# v1.net
KiCad netlist of a schematic drawn in EAGLE
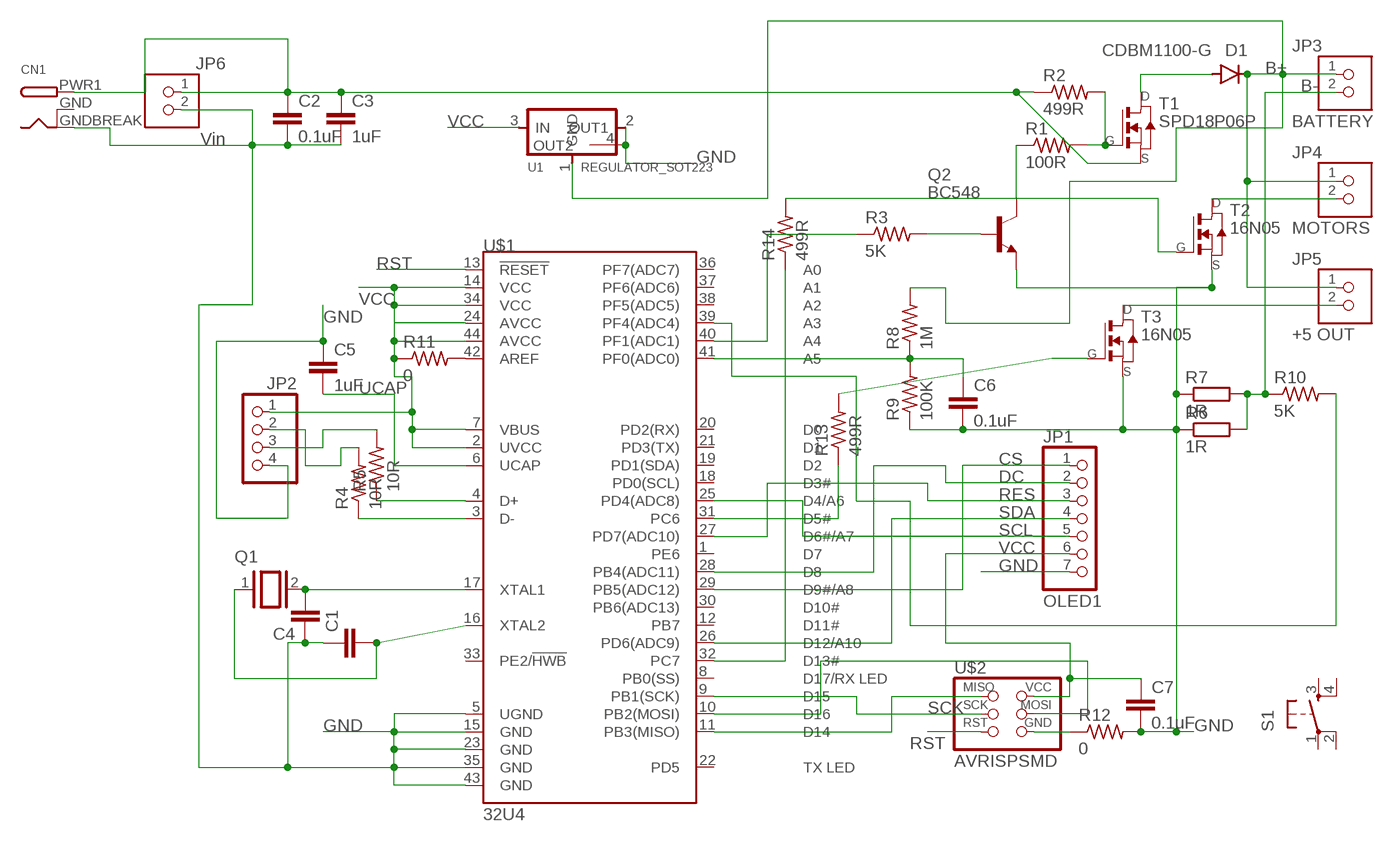
[diagram p0: schematic, sheet 1]

(export (version "E")
  (design (tool "Eeschema 10.0.6"))
  (components
    (comp (ref "C1")
      (value "C-EUC1206")
      (footprint "eagle-import:C1206")
      (libsource (lib "eagle-import") (part "C-EUC1206"))
    )
    (comp (ref "C2")
      (value "0.1uF")
      (footprint "eagle-import:C1206")
      (libsource (lib "eagle-import") (part "C-EUC1206"))
    )
    (comp (ref "C3")
      (value "1uF")
      (footprint "eagle-import:C1206")
      (libsource (lib "eagle-import") (part "C-EUC1206"))
    )
    (comp (ref "C4")
      (value "C-EUC1206")
      (footprint "eagle-import:C1206")
      (libsource (lib "eagle-import") (part "C-EUC1206"))
    )
    (comp (ref "C5")
      (value "1uF")
      (footprint "eagle-import:C1206")
      (libsource (lib "eagle-import") (part "C-EUC1206"))
    )
    (comp (ref "C6")
      (value "0.1uF")
      (footprint "eagle-import:C1206")
      (libsource (lib "eagle-import") (part "C-EUC1206"))
    )
    (comp (ref "C7")
      (value "0.1uF")
      (footprint "eagle-import:C1206")
      (libsource (lib "eagle-import") (part "C-EUC1206"))
    )
    (comp (ref "CN1")
      (value "DCBARRELSMT")
      (footprint "eagle-import:DCJACK_2MM_SMT")
      (libsource (lib "eagle-import") (part "DCBARRELSMT"))
    )
    (comp (ref "D1")
      (value "CDBM1100-G")
      (footprint "eagle-import:MINI-SMA")
      (libsource (lib "eagle-import") (part "CDBM1100-G"))
    )
    (comp (ref "JP1")
      (value "OLED1")
      (footprint "eagle-import:1X07")
      (libsource (lib "eagle-import") (part "PINHD-1X7"))
    )
    (comp (ref "JP2")
      (value "PINHD-1X4")
      (footprint "eagle-import:1X04")
      (libsource (lib "eagle-import") (part "PINHD-1X4"))
    )
    (comp (ref "JP3")
      (value "BATTERY")
      (footprint "eagle-import:ED555DS-2DS")
      (libsource (lib "eagle-import") (part "TERM-1X02-FABLAB"))
    )
    (comp (ref "JP4")
      (value "MOTORS")
      (footprint "eagle-import:ED555DS-2DS")
      (libsource (lib "eagle-import") (part "TERM-1X02-FABLAB"))
    )
    (comp (ref "JP5")
      (value "+5 OUT")
      (footprint "eagle-import:ED555DS-2DS")
      (libsource (lib "eagle-import") (part "TERM-1X02-FABLAB"))
    )
    (comp (ref "JP6")
      (value "Vin")
      (footprint "eagle-import:ED555DS-2DS")
      (libsource (lib "eagle-import") (part "TERM-1X02-FABLAB"))
    )
    (comp (ref "Q1")
      (value "XTAL/S")
      (footprint "eagle-import:QS")
      (libsource (lib "eagle-import") (part "XTAL/S"))
    )
    (comp (ref "Q2")
      (value "BC548")
      (footprint "eagle-import:TO92-EBC")
      (libsource (lib "eagle-import") (part "BC548"))
    )
    (comp (ref "R1")
      (value "100R")
      (footprint "eagle-import:M1206")
      (libsource (lib "eagle-import") (part "R-US_M1206"))
    )
    (comp (ref "R2")
      (value "499R")
      (footprint "eagle-import:M1206")
      (libsource (lib "eagle-import") (part "R-US_M1206"))
    )
    (comp (ref "R3")
      (value "5K")
      (footprint "eagle-import:M1206")
      (libsource (lib "eagle-import") (part "R-US_M1206"))
    )
    (comp (ref "R4")
      (value "10R")
      (footprint "eagle-import:M1206")
      (libsource (lib "eagle-import") (part "R-US_M1206"))
    )
    (comp (ref "R5")
      (value "10R")
      (footprint "eagle-import:M1206")
      (libsource (lib "eagle-import") (part "R-US_M1206"))
    )
    (comp (ref "R6")
      (value "1R")
      (footprint "eagle-import:R6332W")
      (libsource (lib "eagle-import") (part "R-EU_R6332W"))
    )
    (comp (ref "R7")
      (value "1R")
      (footprint "eagle-import:R6332W")
      (libsource (lib "eagle-import") (part "R-EU_R6332W"))
    )
    (comp (ref "R8")
      (value "1M")
      (footprint "eagle-import:M1206")
      (libsource (lib "eagle-import") (part "R-US_M1206"))
    )
    (comp (ref "R9")
      (value "100K")
      (footprint "eagle-import:M1206")
      (libsource (lib "eagle-import") (part "R-US_M1206"))
    )
    (comp (ref "R10")
      (value "5K")
      (footprint "eagle-import:M1206")
      (libsource (lib "eagle-import") (part "R-US_M1206"))
    )
    (comp (ref "R11")
      (value "0")
      (footprint "eagle-import:M1206")
      (libsource (lib "eagle-import") (part "R-US_M1206"))
    )
    (comp (ref "R12")
      (value "0")
      (footprint "eagle-import:M1206")
      (libsource (lib "eagle-import") (part "R-US_M1206"))
    )
    (comp (ref "R13")
      (value "499R")
      (footprint "eagle-import:M1206")
      (libsource (lib "eagle-import") (part "R-US_M1206"))
    )
    (comp (ref "R14")
      (value "499R")
      (footprint "eagle-import:M1206")
      (libsource (lib "eagle-import") (part "R-US_M1206"))
    )
    (comp (ref "S1")
      (value "6MM_SWITCH6MM_SWITCH")
      (footprint "eagle-import:6MM_SWITCH")
      (libsource (lib "eagle-import") (part "6MM_SWITCH6MM_SWITCH"))
    )
    (comp (ref "T1")
      (value "SPD18P06P")
      (footprint "eagle-import:TO252")
      (libsource (lib "eagle-import") (part "NMOSFETTO252"))
    )
    (comp (ref "T2")
      (value "16N05")
      (footprint "eagle-import:TO252")
      (libsource (lib "eagle-import") (part "NMOSFETTO252"))
    )
    (comp (ref "T3")
      (value "16N05")
      (footprint "eagle-import:TO252")
      (libsource (lib "eagle-import") (part "NMOSFETTO252"))
    )
    (comp (ref "U$1")
      (value "32U4")
      (footprint "eagle-import:TQFP44")
      (libsource (lib "eagle-import") (part "ATMEGA32U4TQFP-44"))
    )
    (comp (ref "U$2")
      (value "AVRISPSMD")
      (footprint "eagle-import:2X03SMD")
      (libsource (lib "eagle-import") (part "AVRISPSMD"))
    )
    (comp (ref "U1")
      (value "REGULATOR_SOT223")
      (footprint "eagle-import:SOT223")
      (libsource (lib "eagle-import") (part "REGULATOR_SOT223"))
    )
  )
  (nets
    (net (code "1") (name "/B+") (class "Default")
      (node (ref "D1") (pin "KATHODE") (pinfunction "KATHODE_KATHODE") (pintype "bidirectional"))
      (node (ref "JP3") (pin "1") (pinfunction "1_1") (pintype "passive"))
      (node (ref "JP4") (pin "1") (pinfunction "1_1") (pintype "passive"))
      (node (ref "JP5") (pin "1") (pinfunction "1_1") (pintype "passive"))
      (node (ref "R8") (pin "2") (pinfunction "2_2") (pintype "passive"))
      (node (ref "U1") (pin "1") (pinfunction "GND_1") (pintype "bidirectional"))
    )
    (net (code "2") (name "/B-") (class "Default")
      (node (ref "JP3") (pin "2") (pinfunction "2_2") (pintype "passive"))
      (node (ref "R10") (pin "1") (pinfunction "1_1") (pintype "passive"))
      (node (ref "R6") (pin "2") (pinfunction "2_2") (pintype "passive"))
      (node (ref "R7") (pin "2") (pinfunction "2_2") (pintype "passive"))
    )
    (net (code "3") (name "/CS") (class "Default")
      (node (ref "JP1") (pin "1") (pinfunction "1_1") (pintype "passive"))
      (node (ref "U$1") (pin "29") (pinfunction "PB5(ADC12)_29") (pintype "bidirectional"))
    )
    (net (code "4") (name "/DC") (class "Default")
      (node (ref "JP1") (pin "2") (pinfunction "2_2") (pintype "passive"))
      (node (ref "U$1") (pin "28") (pinfunction "PB4(ADC11)_28") (pintype "bidirectional"))
    )
    (net (code "5") (name "/GND") (class "Default")
      (node (ref "C1") (pin "1") (pinfunction "1_1") (pintype "passive"))
      (node (ref "C2") (pin "2") (pinfunction "2_2") (pintype "passive"))
      (node (ref "C3") (pin "2") (pinfunction "2_2") (pintype "passive"))
      (node (ref "C4") (pin "1") (pinfunction "1_1") (pintype "passive"))
      (node (ref "C5") (pin "1") (pinfunction "1_1") (pintype "passive"))
      (node (ref "C6") (pin "2") (pinfunction "2_2") (pintype "passive"))
      (node (ref "C7") (pin "2") (pinfunction "2_2") (pintype "passive"))
      (node (ref "CN1") (pin "GNDBREAK") (pinfunction "GND_GNDBREAK") (pintype "power_in"))
      (node (ref "JP1") (pin "7") (pinfunction "7_7") (pintype "passive"))
      (node (ref "JP2") (pin "4") (pinfunction "4_4") (pintype "passive"))
      (node (ref "JP6") (pin "2") (pinfunction "2_2") (pintype "passive"))
      (node (ref "Q2") (pin "E") (pinfunction "E_E") (pintype "passive"))
      (node (ref "R12") (pin "2") (pinfunction "2_2") (pintype "passive"))
      (node (ref "R6") (pin "1") (pinfunction "1_1") (pintype "passive"))
      (node (ref "R7") (pin "1") (pinfunction "1_1") (pintype "passive"))
      (node (ref "R9") (pin "1") (pinfunction "1_1") (pintype "passive"))
      (node (ref "T2") (pin "2") (pinfunction "S_2") (pintype "passive"))
      (node (ref "T3") (pin "2") (pinfunction "S_2") (pintype "passive"))
      (node (ref "U$1") (pin "15") (pinfunction "GND_15") (pintype "bidirectional"))
      (node (ref "U$1") (pin "23") (pinfunction "GND_23") (pintype "bidirectional"))
      (node (ref "U$1") (pin "35") (pinfunction "GND_35") (pintype "bidirectional"))
      (node (ref "U$1") (pin "43") (pinfunction "GND_43") (pintype "bidirectional"))
      (node (ref "U$1") (pin "5") (pinfunction "UGND_5") (pintype "bidirectional"))
      (node (ref "U1") (pin "2") (pinfunction "OUT1_2") (pintype "bidirectional"))
      (node (ref "U1") (pin "4") (pinfunction "OUT2_4") (pintype "bidirectional"))
    )
    (net (code "6") (name "/GNDBREAK") (class "Default")
      (node (ref "CN1") (pin "GND") (pinfunction "GNDBREAK_GND") (pintype "power_in"))
    )
    (net (code "7") (name "/RES") (class "Default")
      (node (ref "JP1") (pin "3") (pinfunction "3_3") (pintype "passive"))
      (node (ref "U$1") (pin "27") (pinfunction "PD7(ADC10)_27") (pintype "bidirectional"))
    )
    (net (code "8") (name "/RST") (class "Default")
      (node (ref "U$1") (pin "13") (pinfunction "~{RESET}_13") (pintype "bidirectional"))
      (node (ref "U$2") (pin "5") (pinfunction "RST_5") (pintype "passive"))
    )
    (net (code "9") (name "/SCK") (class "Default")
      (node (ref "U$1") (pin "9") (pinfunction "PB1(SCK)_9") (pintype "bidirectional"))
      (node (ref "U$2") (pin "3") (pinfunction "SCK_3") (pintype "passive"))
    )
    (net (code "10") (name "/SCL") (class "Default")
      (node (ref "JP1") (pin "5") (pinfunction "5_5") (pintype "passive"))
      (node (ref "U$1") (pin "25") (pinfunction "PD4(ADC8)_25") (pintype "bidirectional"))
    )
    (net (code "11") (name "/SDA") (class "Default")
      (node (ref "JP1") (pin "4") (pinfunction "4_4") (pintype "passive"))
      (node (ref "U$1") (pin "26") (pinfunction "PD6(ADC9)_26") (pintype "bidirectional"))
    )
    (net (code "12") (name "/UCAP") (class "Default")
      (node (ref "C5") (pin "2") (pinfunction "2_2") (pintype "passive"))
      (node (ref "U$1") (pin "6") (pinfunction "UCAP_6") (pintype "bidirectional"))
    )
    (net (code "13") (name "/VCC") (class "Default")
      (node (ref "C7") (pin "1") (pinfunction "1_1") (pintype "passive"))
      (node (ref "JP1") (pin "6") (pinfunction "6_6") (pintype "passive"))
      (node (ref "JP2") (pin "1") (pinfunction "1_1") (pintype "passive"))
      (node (ref "R11") (pin "1") (pinfunction "1_1") (pintype "passive"))
      (node (ref "U$1") (pin "14") (pinfunction "VCC_14") (pintype "bidirectional"))
      (node (ref "U$1") (pin "2") (pinfunction "UVCC_2") (pintype "bidirectional"))
      (node (ref "U$1") (pin "24") (pinfunction "AVCC_24") (pintype "bidirectional"))
      (node (ref "U$1") (pin "34") (pinfunction "VCC_34") (pintype "bidirectional"))
      (node (ref "U$1") (pin "44") (pinfunction "AVCC_44") (pintype "bidirectional"))
      (node (ref "U$1") (pin "7") (pinfunction "VBUS_7") (pintype "bidirectional"))
      (node (ref "U$2") (pin "2") (pinfunction "VCC_2") (pintype "passive"))
      (node (ref "U1") (pin "3") (pinfunction "IN_3") (pintype "bidirectional"))
    )
    (net (code "14") (name "Net-(CN1-PWR)") (class "Default")
      (node (ref "C2") (pin "1") (pinfunction "1_1") (pintype "passive"))
      (node (ref "C3") (pin "1") (pinfunction "1_1") (pintype "passive"))
      (node (ref "CN1") (pin "PWR1") (pinfunction "PWR_PWR1") (pintype "power_in"))
      (node (ref "JP6") (pin "1") (pinfunction "1_1") (pintype "passive"))
      (node (ref "R2") (pin "1") (pinfunction "1_1") (pintype "passive"))
      (node (ref "T1") (pin "2") (pinfunction "S_2") (pintype "passive"))
    )
    (net (code "15") (name "Net-(JP2-Pad2)") (class "Default")
      (node (ref "JP2") (pin "2") (pinfunction "2_2") (pintype "passive"))
      (node (ref "R4") (pin "2") (pinfunction "2_2") (pintype "passive"))
    )
    (net (code "16") (name "Net-(JP2-Pad3)") (class "Default")
      (node (ref "JP2") (pin "3") (pinfunction "3_3") (pintype "passive"))
      (node (ref "R5") (pin "2") (pinfunction "2_2") (pintype "passive"))
    )
    (net (code "17") (name "Net-(Q2-PadB)") (class "Default")
      (node (ref "Q2") (pin "B") (pinfunction "B_B") (pintype "passive"))
      (node (ref "R3") (pin "2") (pinfunction "2_2") (pintype "passive"))
    )
    (net (code "18") (name "Net-(Q2-PadC)") (class "Default")
      (node (ref "Q2") (pin "C") (pinfunction "C_C") (pintype "passive"))
      (node (ref "R1") (pin "1") (pinfunction "1_1") (pintype "passive"))
    )
    (net (code "19") (name "Net-(T1-D)") (class "Default")
      (node (ref "D1") (pin "ANODE") (pinfunction "ANODE_ANODE") (pintype "bidirectional"))
      (node (ref "T1") (pin "3") (pinfunction "D_3") (pintype "passive"))
    )
    (net (code "20") (name "Net-(T1-G)") (class "Default")
      (node (ref "R1") (pin "2") (pinfunction "2_2") (pintype "passive"))
      (node (ref "R2") (pin "2") (pinfunction "2_2") (pintype "passive"))
      (node (ref "T1") (pin "1") (pinfunction "G_1") (pintype "passive"))
    )
    (net (code "21") (name "Net-(T2-D)") (class "Default")
      (node (ref "JP4") (pin "2") (pinfunction "2_2") (pintype "passive"))
      (node (ref "T2") (pin "3") (pinfunction "D_3") (pintype "passive"))
    )
    (net (code "22") (name "Net-(T2-G)") (class "Default")
      (node (ref "R14") (pin "2") (pinfunction "2_2") (pintype "passive"))
      (node (ref "T2") (pin "1") (pinfunction "G_1") (pintype "passive"))
    )
    (net (code "23") (name "Net-(T3-D)") (class "Default")
      (node (ref "JP5") (pin "2") (pinfunction "2_2") (pintype "passive"))
      (node (ref "T3") (pin "3") (pinfunction "D_3") (pintype "passive"))
    )
    (net (code "24") (name "Net-(T3-G)") (class "Default")
      (node (ref "R13") (pin "2") (pinfunction "2_2") (pintype "passive"))
      (node (ref "T3") (pin "1") (pinfunction "G_1") (pintype "passive"))
    )
    (net (code "25") (name "Net-(U$1-AREF)") (class "Default")
      (node (ref "R11") (pin "2") (pinfunction "2_2") (pintype "passive"))
      (node (ref "U$1") (pin "42") (pinfunction "AREF_42") (pintype "bidirectional"))
    )
    (net (code "26") (name "Net-(U$1-D+)") (class "Default")
      (node (ref "R5") (pin "1") (pinfunction "1_1") (pintype "passive"))
      (node (ref "U$1") (pin "4") (pinfunction "D+_4") (pintype "bidirectional"))
    )
    (net (code "27") (name "Net-(U$1-D-)") (class "Default")
      (node (ref "R4") (pin "1") (pinfunction "1_1") (pintype "passive"))
      (node (ref "U$1") (pin "3") (pinfunction "D-_3") (pintype "bidirectional"))
    )
    (net (code "28") (name "Net-(U$1-PB2(MOSI))") (class "Default")
      (node (ref "U$1") (pin "10") (pinfunction "PB2(MOSI)_10") (pintype "bidirectional"))
      (node (ref "U$2") (pin "4") (pinfunction "MOSI_4") (pintype "passive"))
    )
    (net (code "29") (name "Net-(U$1-PB3(MISO))") (class "Default")
      (node (ref "U$1") (pin "11") (pinfunction "PB3(MISO)_11") (pintype "bidirectional"))
      (node (ref "U$2") (pin "1") (pinfunction "MISO_1") (pintype "passive"))
    )
    (net (code "30") (name "Net-(U$1-PC6)") (class "Default")
      (node (ref "R13") (pin "1") (pinfunction "1_1") (pintype "passive"))
      (node (ref "U$1") (pin "31") (pinfunction "PC6_31") (pintype "bidirectional"))
    )
    (net (code "31") (name "Net-(U$1-PC7)") (class "Default")
      (node (ref "R14") (pin "1") (pinfunction "1_1") (pintype "passive"))
      (node (ref "U$1") (pin "32") (pinfunction "PC7_32") (pintype "bidirectional"))
    )
    (net (code "32") (name "Net-(U$1-PF0(ADC0))") (class "Default")
      (node (ref "C6") (pin "1") (pinfunction "1_1") (pintype "passive"))
      (node (ref "R8") (pin "1") (pinfunction "1_1") (pintype "passive"))
      (node (ref "R9") (pin "2") (pinfunction "2_2") (pintype "passive"))
      (node (ref "U$1") (pin "41") (pinfunction "PF0(ADC0)_41") (pintype "bidirectional"))
    )
    (net (code "33") (name "Net-(U$1-PF1(ADC1))") (class "Default")
      (node (ref "R3") (pin "1") (pinfunction "1_1") (pintype "passive"))
      (node (ref "U$1") (pin "40") (pinfunction "PF1(ADC1)_40") (pintype "bidirectional"))
    )
    (net (code "34") (name "Net-(U$1-PF4(ADC4))") (class "Default")
      (node (ref "R10") (pin "2") (pinfunction "2_2") (pintype "passive"))
      (node (ref "U$1") (pin "39") (pinfunction "PF4(ADC4)_39") (pintype "bidirectional"))
    )
    (net (code "35") (name "Net-(U$1-XTAL1)") (class "Default")
      (node (ref "C4") (pin "2") (pinfunction "2_2") (pintype "passive"))
      (node (ref "Q1") (pin "2") (pinfunction "2_2") (pintype "passive"))
      (node (ref "U$1") (pin "17") (pinfunction "XTAL1_17") (pintype "bidirectional"))
    )
    (net (code "36") (name "Net-(U$1-XTAL2)") (class "Default")
      (node (ref "C1") (pin "2") (pinfunction "2_2") (pintype "passive"))
      (node (ref "Q1") (pin "1") (pinfunction "1_1") (pintype "passive"))
      (node (ref "U$1") (pin "16") (pinfunction "XTAL2_16") (pintype "bidirectional"))
    )
    (net (code "37") (name "Net-(U$2-GND)") (class "Default")
      (node (ref "R12") (pin "1") (pinfunction "1_1") (pintype "passive"))
      (node (ref "U$2") (pin "6") (pinfunction "GND_6") (pintype "passive"))
    )
    (net (code "38") (name "unconnected-(S1-P-Pad1)") (class "Default")
      (node (ref "S1") (pin "1") (pinfunction "P_1") (pintype "passive"))
    )
    (net (code "39") (name "unconnected-(S1-P1-Pad2)") (class "Default")
      (node (ref "S1") (pin "2") (pinfunction "P1_2") (pintype "passive"))
    )
    (net (code "40") (name "unconnected-(S1-S-Pad3)") (class "Default")
      (node (ref "S1") (pin "3") (pinfunction "S_3") (pintype "passive"))
    )
    (net (code "41") (name "unconnected-(S1-S1-Pad4)") (class "Default")
      (node (ref "S1") (pin "4") (pinfunction "S1_4") (pintype "passive"))
    )
    (net (code "42") (name "unconnected-(U$1-PB0(SS)-Pad8)") (class "Default")
      (node (ref "U$1") (pin "8") (pinfunction "PB0(SS)_8") (pintype "bidirectional"))
    )
    (net (code "43") (name "unconnected-(U$1-PB6(ADC13)-Pad30)") (class "Default")
      (node (ref "U$1") (pin "30") (pinfunction "PB6(ADC13)_30") (pintype "bidirectional"))
    )
    (net (code "44") (name "unconnected-(U$1-PB7-Pad12)") (class "Default")
      (node (ref "U$1") (pin "12") (pinfunction "PB7_12") (pintype "bidirectional"))
    )
    (net (code "45") (name "unconnected-(U$1-PD0(SCL)-Pad18)") (class "Default")
      (node (ref "U$1") (pin "18") (pinfunction "PD0(SCL)_18") (pintype "bidirectional"))
    )
    (net (code "46") (name "unconnected-(U$1-PD1(SDA)-Pad19)") (class "Default")
      (node (ref "U$1") (pin "19") (pinfunction "PD1(SDA)_19") (pintype "bidirectional"))
    )
    (net (code "47") (name "unconnected-(U$1-PD2(RX)-Pad20)") (class "Default")
      (node (ref "U$1") (pin "20") (pinfunction "PD2(RX)_20") (pintype "bidirectional"))
    )
    (net (code "48") (name "unconnected-(U$1-PD3(TX)-Pad21)") (class "Default")
      (node (ref "U$1") (pin "21") (pinfunction "PD3(TX)_21") (pintype "bidirectional"))
    )
    (net (code "49") (name "unconnected-(U$1-PD5-Pad22)") (class "Default")
      (node (ref "U$1") (pin "22") (pinfunction "PD5_22") (pintype "bidirectional"))
    )
    (net (code "50") (name "unconnected-(U$1-PE2{slash}~{HWB}-Pad33)") (class "Default")
      (node (ref "U$1") (pin "33") (pinfunction "PE2/~{HWB}_33") (pintype "bidirectional"))
    )
    (net (code "51") (name "unconnected-(U$1-PE6-Pad1)") (class "Default")
      (node (ref "U$1") (pin "1") (pinfunction "PE6_1") (pintype "bidirectional"))
    )
    (net (code "52") (name "unconnected-(U$1-PF5(ADC5)-Pad38)") (class "Default")
      (node (ref "U$1") (pin "38") (pinfunction "PF5(ADC5)_38") (pintype "bidirectional"))
    )
    (net (code "53") (name "unconnected-(U$1-PF6(ADC6)-Pad37)") (class "Default")
      (node (ref "U$1") (pin "37") (pinfunction "PF6(ADC6)_37") (pintype "bidirectional"))
    )
    (net (code "54") (name "unconnected-(U$1-PF7(ADC7)-Pad36)") (class "Default")
      (node (ref "U$1") (pin "36") (pinfunction "PF7(ADC7)_36") (pintype "bidirectional"))
    )
  )
)
